# rc32kram62256ram_v1.net
KiCad netlist of a schematic drawn in EAGLE
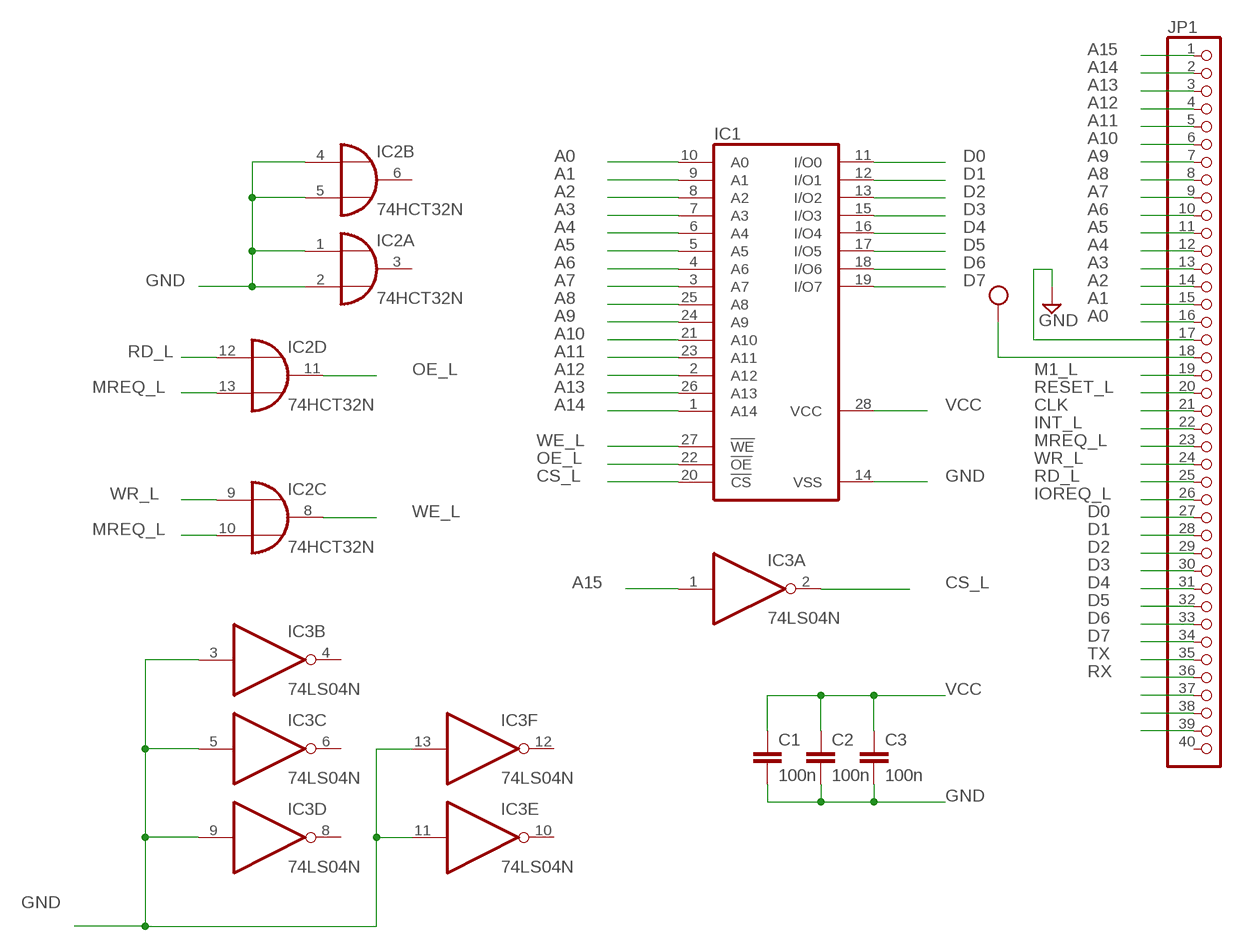
[diagram p0: schematic, sheet 1]

(export (version "E")
  (design (tool "Eeschema 10.0.6"))
  (components
    (comp (ref "C1")
      (value "100n")
      (footprint "eagle-import:C050-025X075")
      (libsource (lib "eagle-import") (part "C-EU050-025X075"))
    )
    (comp (ref "C2")
      (value "100n")
      (footprint "eagle-import:C050-025X075")
      (libsource (lib "eagle-import") (part "C-EU050-025X075"))
    )
    (comp (ref "C3")
      (value "100n")
      (footprint "eagle-import:C050-025X075")
      (libsource (lib "eagle-import") (part "C-EU050-025X075"))
    )
    (comp (ref "IC1")
      (value "62256P")
      (footprint "eagle-import:DIL28-6")
      (libsource (lib "eagle-import") (part "62256P"))
    )
    (comp (ref "IC2")
      (value "74HCT32N")
      (footprint "eagle-import:DIL14")
      (libsource (lib "eagle-import") (part "7432NHCT"))
    )
    (comp (ref "IC3")
      (value "74LS04N")
      (footprint "eagle-import:DIL14")
      (libsource (lib "eagle-import") (part "7404NLS"))
    )
    (comp (ref "JP1")
      (value "PINHD-1X40")
      (footprint "eagle-import:1X40")
      (libsource (lib "eagle-import") (part "PINHD-1X40"))
    )
  )
  (nets
    (net (code "1") (name "/A0") (class "Default")
      (node (ref "IC1") (pin "10") (pinfunction "A0_10") (pintype "input"))
      (node (ref "JP1") (pin "16") (pinfunction "16_16") (pintype "passive"))
    )
    (net (code "2") (name "/A1") (class "Default")
      (node (ref "IC1") (pin "9") (pinfunction "A1_9") (pintype "input"))
      (node (ref "JP1") (pin "15") (pinfunction "15_15") (pintype "passive"))
    )
    (net (code "3") (name "/A2") (class "Default")
      (node (ref "IC1") (pin "8") (pinfunction "A2_8") (pintype "input"))
      (node (ref "JP1") (pin "14") (pinfunction "14_14") (pintype "passive"))
    )
    (net (code "4") (name "/A3") (class "Default")
      (node (ref "IC1") (pin "7") (pinfunction "A3_7") (pintype "input"))
      (node (ref "JP1") (pin "13") (pinfunction "13_13") (pintype "passive"))
    )
    (net (code "5") (name "/A4") (class "Default")
      (node (ref "IC1") (pin "6") (pinfunction "A4_6") (pintype "input"))
      (node (ref "JP1") (pin "12") (pinfunction "12_12") (pintype "passive"))
    )
    (net (code "6") (name "/A5") (class "Default")
      (node (ref "IC1") (pin "5") (pinfunction "A5_5") (pintype "input"))
      (node (ref "JP1") (pin "11") (pinfunction "11_11") (pintype "passive"))
    )
    (net (code "7") (name "/A6") (class "Default")
      (node (ref "IC1") (pin "4") (pinfunction "A6_4") (pintype "input"))
      (node (ref "JP1") (pin "10") (pinfunction "10_10") (pintype "passive"))
    )
    (net (code "8") (name "/A7") (class "Default")
      (node (ref "IC1") (pin "3") (pinfunction "A7_3") (pintype "input"))
      (node (ref "JP1") (pin "9") (pinfunction "9_9") (pintype "passive"))
    )
    (net (code "9") (name "/A8") (class "Default")
      (node (ref "IC1") (pin "25") (pinfunction "A8_25") (pintype "input"))
      (node (ref "JP1") (pin "8") (pinfunction "8_8") (pintype "passive"))
    )
    (net (code "10") (name "/A9") (class "Default")
      (node (ref "IC1") (pin "24") (pinfunction "A9_24") (pintype "input"))
      (node (ref "JP1") (pin "7") (pinfunction "7_7") (pintype "passive"))
    )
    (net (code "11") (name "/A10") (class "Default")
      (node (ref "IC1") (pin "21") (pinfunction "A10_21") (pintype "input"))
      (node (ref "JP1") (pin "6") (pinfunction "6_6") (pintype "passive"))
    )
    (net (code "12") (name "/A11") (class "Default")
      (node (ref "IC1") (pin "23") (pinfunction "A11_23") (pintype "input"))
      (node (ref "JP1") (pin "5") (pinfunction "5_5") (pintype "passive"))
    )
    (net (code "13") (name "/A12") (class "Default")
      (node (ref "IC1") (pin "2") (pinfunction "A12_2") (pintype "input"))
      (node (ref "JP1") (pin "4") (pinfunction "4_4") (pintype "passive"))
    )
    (net (code "14") (name "/A13") (class "Default")
      (node (ref "IC1") (pin "26") (pinfunction "A13_26") (pintype "input"))
      (node (ref "JP1") (pin "3") (pinfunction "3_3") (pintype "passive"))
    )
    (net (code "15") (name "/A14") (class "Default")
      (node (ref "IC1") (pin "1") (pinfunction "A14_1") (pintype "input"))
      (node (ref "JP1") (pin "2") (pinfunction "2_2") (pintype "passive"))
    )
    (net (code "16") (name "/A15") (class "Default")
      (node (ref "IC3") (pin "1") (pinfunction "I_1") (pintype "input"))
      (node (ref "JP1") (pin "1") (pinfunction "1_1") (pintype "passive"))
    )
    (net (code "17") (name "/CLK") (class "Default")
      (node (ref "JP1") (pin "21") (pinfunction "21_21") (pintype "passive"))
    )
    (net (code "18") (name "/CS_L") (class "Default")
      (node (ref "IC1") (pin "20") (pinfunction "~{CS}_20") (pintype "input"))
      (node (ref "IC3") (pin "2") (pinfunction "O_2") (pintype "output"))
    )
    (net (code "19") (name "/D0") (class "Default")
      (node (ref "IC1") (pin "11") (pinfunction "I/O0_11") (pintype "bidirectional"))
      (node (ref "JP1") (pin "27") (pinfunction "27_27") (pintype "passive"))
    )
    (net (code "20") (name "/D1") (class "Default")
      (node (ref "IC1") (pin "12") (pinfunction "I/O1_12") (pintype "bidirectional"))
      (node (ref "JP1") (pin "28") (pinfunction "28_28") (pintype "passive"))
    )
    (net (code "21") (name "/D2") (class "Default")
      (node (ref "IC1") (pin "13") (pinfunction "I/O2_13") (pintype "bidirectional"))
      (node (ref "JP1") (pin "29") (pinfunction "29_29") (pintype "passive"))
    )
    (net (code "22") (name "/D3") (class "Default")
      (node (ref "IC1") (pin "15") (pinfunction "I/O3_15") (pintype "bidirectional"))
      (node (ref "JP1") (pin "30") (pinfunction "30_30") (pintype "passive"))
    )
    (net (code "23") (name "/D4") (class "Default")
      (node (ref "IC1") (pin "16") (pinfunction "I/O4_16") (pintype "bidirectional"))
      (node (ref "JP1") (pin "31") (pinfunction "31_31") (pintype "passive"))
    )
    (net (code "24") (name "/D5") (class "Default")
      (node (ref "IC1") (pin "17") (pinfunction "I/O5_17") (pintype "bidirectional"))
      (node (ref "JP1") (pin "32") (pinfunction "32_32") (pintype "passive"))
    )
    (net (code "25") (name "/D6") (class "Default")
      (node (ref "IC1") (pin "18") (pinfunction "I/O6_18") (pintype "bidirectional"))
      (node (ref "JP1") (pin "33") (pinfunction "33_33") (pintype "passive"))
    )
    (net (code "26") (name "/D7") (class "Default")
      (node (ref "IC1") (pin "19") (pinfunction "I/O7_19") (pintype "bidirectional"))
      (node (ref "JP1") (pin "34") (pinfunction "34_34") (pintype "passive"))
    )
    (net (code "27") (name "/INT_L") (class "Default")
      (node (ref "JP1") (pin "22") (pinfunction "22_22") (pintype "passive"))
    )
    (net (code "28") (name "/IOREQ_L") (class "Default")
      (node (ref "JP1") (pin "26") (pinfunction "26_26") (pintype "passive"))
    )
    (net (code "29") (name "/M1_L") (class "Default")
      (node (ref "JP1") (pin "19") (pinfunction "19_19") (pintype "passive"))
    )
    (net (code "30") (name "/MREQ_L") (class "Default")
      (node (ref "IC2") (pin "10") (pinfunction "I1_10") (pintype "input"))
      (node (ref "IC2") (pin "13") (pinfunction "I1_13") (pintype "input"))
      (node (ref "JP1") (pin "23") (pinfunction "23_23") (pintype "passive"))
    )
    (net (code "31") (name "/OE_L") (class "Default")
      (node (ref "IC1") (pin "22") (pinfunction "~{OE}_22") (pintype "input"))
      (node (ref "IC2") (pin "11") (pinfunction "O_11") (pintype "output"))
    )
    (net (code "32") (name "/RD_L") (class "Default")
      (node (ref "IC2") (pin "12") (pinfunction "I0_12") (pintype "input"))
      (node (ref "JP1") (pin "25") (pinfunction "25_25") (pintype "passive"))
    )
    (net (code "33") (name "/RESET_L") (class "Default")
      (node (ref "JP1") (pin "20") (pinfunction "20_20") (pintype "passive"))
    )
    (net (code "34") (name "/RX") (class "Default")
      (node (ref "JP1") (pin "36") (pinfunction "36_36") (pintype "passive"))
    )
    (net (code "35") (name "/TX") (class "Default")
      (node (ref "JP1") (pin "35") (pinfunction "35_35") (pintype "passive"))
    )
    (net (code "36") (name "/WE_L") (class "Default")
      (node (ref "IC1") (pin "27") (pinfunction "~{WE}_27") (pintype "input"))
      (node (ref "IC2") (pin "8") (pinfunction "O_8") (pintype "output"))
    )
    (net (code "37") (name "/WR_L") (class "Default")
      (node (ref "IC2") (pin "9") (pinfunction "I0_9") (pintype "input"))
      (node (ref "JP1") (pin "24") (pinfunction "24_24") (pintype "passive"))
    )
    (net (code "38") (name "GND") (class "Default")
      (node (ref "C1") (pin "2") (pinfunction "2_2") (pintype "passive"))
      (node (ref "C2") (pin "2") (pinfunction "2_2") (pintype "passive"))
      (node (ref "C3") (pin "2") (pinfunction "2_2") (pintype "passive"))
      (node (ref "IC1") (pin "14") (pinfunction "VSS_14") (pintype "power_in"))
      (node (ref "IC2") (pin "1") (pinfunction "I0_1") (pintype "input"))
      (node (ref "IC2") (pin "2") (pinfunction "I1_2") (pintype "input"))
      (node (ref "IC2") (pin "4") (pinfunction "I0_4") (pintype "input"))
      (node (ref "IC2") (pin "5") (pinfunction "I1_5") (pintype "input"))
      (node (ref "IC3") (pin "11") (pinfunction "I_11") (pintype "input"))
      (node (ref "IC3") (pin "13") (pinfunction "I_13") (pintype "input"))
      (node (ref "IC3") (pin "3") (pinfunction "I_3") (pintype "input"))
      (node (ref "IC3") (pin "5") (pinfunction "I_5") (pintype "input"))
      (node (ref "IC3") (pin "9") (pinfunction "I_9") (pintype "input"))
      (node (ref "JP1") (pin "17") (pinfunction "17_17") (pintype "passive"))
    )
    (net (code "39") (name "VCC") (class "Default")
      (node (ref "C1") (pin "1") (pinfunction "1_1") (pintype "passive"))
      (node (ref "C2") (pin "1") (pinfunction "1_1") (pintype "passive"))
      (node (ref "C3") (pin "1") (pinfunction "1_1") (pintype "passive"))
      (node (ref "IC1") (pin "28") (pinfunction "VCC_28") (pintype "power_in"))
      (node (ref "JP1") (pin "18") (pinfunction "18_18") (pintype "passive"))
    )
    (net (code "40") (name "unconnected-(IC2A-O-Pad3)") (class "Default")
      (node (ref "IC2") (pin "3") (pinfunction "O_3") (pintype "output"))
    )
    (net (code "41") (name "unconnected-(IC2B-O-Pad6)") (class "Default")
      (node (ref "IC2") (pin "6") (pinfunction "O_6") (pintype "output"))
    )
    (net (code "42") (name "unconnected-(IC3B-O-Pad4)") (class "Default")
      (node (ref "IC3") (pin "4") (pinfunction "O_4") (pintype "output"))
    )
    (net (code "43") (name "unconnected-(IC3C-O-Pad6)") (class "Default")
      (node (ref "IC3") (pin "6") (pinfunction "O_6") (pintype "output"))
    )
    (net (code "44") (name "unconnected-(IC3D-O-Pad8)") (class "Default")
      (node (ref "IC3") (pin "8") (pinfunction "O_8") (pintype "output"))
    )
    (net (code "45") (name "unconnected-(IC3E-O-Pad10)") (class "Default")
      (node (ref "IC3") (pin "10") (pinfunction "O_10") (pintype "output"))
    )
    (net (code "46") (name "unconnected-(IC3F-O-Pad12)") (class "Default")
      (node (ref "IC3") (pin "12") (pinfunction "O_12") (pintype "output"))
    )
    (net (code "47") (name "unconnected-(JP1-Pad37)") (class "Default")
      (node (ref "JP1") (pin "37") (pinfunction "37_37") (pintype "passive"))
    )
    (net (code "48") (name "unconnected-(JP1-Pad38)") (class "Default")
      (node (ref "JP1") (pin "38") (pinfunction "38_38") (pintype "passive"))
    )
    (net (code "49") (name "unconnected-(JP1-Pad39)") (class "Default")
      (node (ref "JP1") (pin "39") (pinfunction "39_39") (pintype "passive"))
    )
    (net (code "50") (name "unconnected-(JP1-Pad40)") (class "Default")
      (node (ref "JP1") (pin "40") (pinfunction "40_40") (pintype "passive"))
    )
  )
)
